# Cosmolink_Sheet.net
KiCad netlist of a schematic drawn in Altium Designer
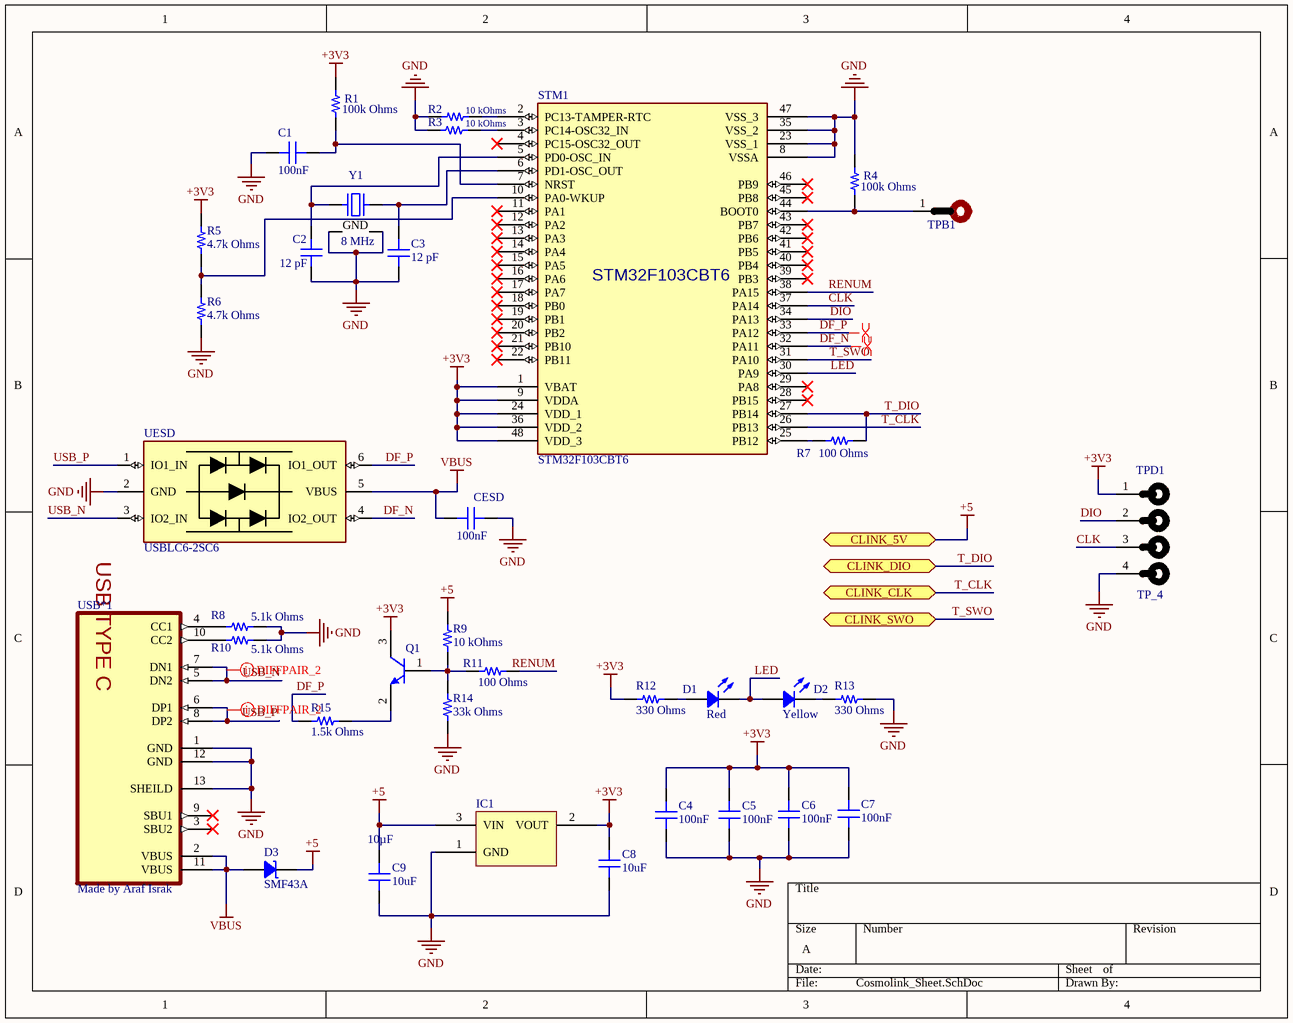
[diagram p0: Cosmolink_Sheet.SchDoc]

(export (version "E")
  (design (tool "Eeschema 10.0.6"))
  (components
    (comp (ref "C1")
      (value "0.1µF")
      (footprint "CAP 0603_1608")
      (description "CAP CER 0.1UF 100V X7R 0603")
      (fields
        (field (name "PART NUMBER") "06031C104KAT2A")
        (field (name "CAPACITANCE") "100nF")
        (field (name "MANUFACTURER") "AVX Corporation")
      )
      (libsource (lib "Celestial Altium Library - altium_library") (part "Capacitor"))
    )
    (comp (ref "C2")
      (value "12 pF")
      (footprint "CAP 0603_1608")
      (description "HIGH-Q MLCC (CF): 0603, 22 PF (1")
      (fields
        (field (name "PART NUMBER") "C06CF220F-9ZN-X0T")
        (field (name "CAPACITANCE") "12 pF")
        (field (name "MANUFACTURER") "Knowles Dielectric Labs")
      )
      (libsource (lib "Celestial Altium Library - altium_library") (part "Capacitor"))
    )
    (comp (ref "C3")
      (value "12 pF")
      (footprint "CAP 0603_1608")
      (description "HIGH-Q MLCC (CF): 0603, 22 PF (1")
      (fields
        (field (name "PART NUMBER") "C06CF220F-9ZN-X0T")
        (field (name "CAPACITANCE") "12 pF")
        (field (name "MANUFACTURER") "Knowles Dielectric Labs")
      )
      (libsource (lib "Celestial Altium Library - altium_library") (part "Capacitor"))
    )
    (comp (ref "C4")
      (value "0.1µF")
      (footprint "CAP 0603_1608")
      (description "CAP CER 0.1UF 100V X7R 0603")
      (fields
        (field (name "PART NUMBER") "06031C104KAT2A")
        (field (name "CAPACITANCE") "100nF")
        (field (name "MANUFACTURER") "AVX Corporation")
      )
      (libsource (lib "Celestial Altium Library - altium_library") (part "Capacitor"))
    )
    (comp (ref "C5")
      (value "0.1µF")
      (footprint "CAP 0603_1608")
      (description "CAP CER 0.1UF 100V X7R 0603")
      (fields
        (field (name "PART NUMBER") "06031C104KAT2A")
        (field (name "CAPACITANCE") "100nF")
        (field (name "MANUFACTURER") "AVX Corporation")
      )
      (libsource (lib "Celestial Altium Library - altium_library") (part "Capacitor"))
    )
    (comp (ref "C6")
      (value "0.1µF")
      (footprint "CAP 0603_1608")
      (description "CAP CER 0.1UF 100V X7R 0603")
      (fields
        (field (name "PART NUMBER") "06031C104KAT2A")
        (field (name "CAPACITANCE") "100nF")
        (field (name "MANUFACTURER") "AVX Corporation")
      )
      (libsource (lib "Celestial Altium Library - altium_library") (part "Capacitor"))
    )
    (comp (ref "C7")
      (value "0.1µF")
      (footprint "CAP 0603_1608")
      (description "CAP CER 0.1UF 100V X7R 0603")
      (fields
        (field (name "PART NUMBER") "06031C104KAT2A")
        (field (name "CAPACITANCE") "100nF")
        (field (name "MANUFACTURER") "AVX Corporation")
      )
      (libsource (lib "Celestial Altium Library - altium_library") (part "Capacitor"))
    )
    (comp (ref "C8")
      (value "10µF")
      (footprint "CAP 0603_1608")
      (description "CAP CER 0.1UF 100V X7R 0603")
      (fields
        (field (name "PART NUMBER") "06031C104KAT2A")
        (field (name "CAPACITANCE") "10uF")
        (field (name "MANUFACTURER") "AVX Corporation")
      )
      (libsource (lib "Celestial Altium Library - altium_library") (part "Capacitor"))
    )
    (comp (ref "C9")
      (value "10µF")
      (footprint "CAP 0603_1608")
      (description "CAP CER 0.1UF 100V X7R 0603")
      (fields
        (field (name "PART NUMBER") "06031C104KAT2A")
        (field (name "CAPACITANCE") "10uF")
        (field (name "MANUFACTURER") "AVX Corporation")
      )
      (libsource (lib "Celestial Altium Library - altium_library") (part "Capacitor"))
    )
    (comp (ref "CESD")
      (value "0.1µF")
      (footprint "CAP 0603_1608")
      (description "CAP CER 0.1UF 100V X7R 0603")
      (fields
        (field (name "PART NUMBER") "06031C104KAT2A")
        (field (name "CAPACITANCE") "100nF")
        (field (name "MANUFACTURER") "AVX Corporation")
      )
      (libsource (lib "Celestial Altium Library - altium_library") (part "Capacitor"))
    )
    (comp (ref "D1")
      (value "Red")
      (footprint "LED 0603_1608 RED")
      (description "LED RED DIFFUSED 1608 SMD")
      (fields
        (field (name "PART NUMBER") "VFHR1111C-3BY2A-TR")
        (field (name "MANUFACTURER") "Stanley Electric Co")
      )
      (libsource (lib "Celestial Altium Library - altium_library") (part "LED"))
    )
    (comp (ref "D2")
      (value "Yellow")
      (footprint "LED 0603_1608 YELLOW")
      (description "LED YELLOW 0603 SMD")
      (fields (field (name "PART NUMBER") "5973405507F") (field (name "MANUFACTURER") "Dialight"))
      (libsource (lib "Celestial Altium Library - altium_library") (part "LED"))
    )
    (comp (ref "D3")
      (value "SMF43A")
      (footprint "SOD123F")
      (description "TVS SOD123FL 43V 200W UNIDIR")
      (fields (field (name "MANUFACTURER") "Littelfuse Inc."))
      (libsource (lib "Celestial Altium Library - altium_library") (part "DIODE TVS UNI"))
    )
    (comp (ref "IC1")
      (value "AP2138N-3.3TRG1")
      (footprint "DIODES SOT-23-3 N")
      (description "IC REG LINEAR 3.3V 250MA SOT23-3")
      (fields (field (name "MANUFACTURER") "Diodes Incorporated"))
      (libsource (lib "Celestial Altium Library - altium_library") (part "Diodes Inc AP2138 3PIN"))
    )
    (comp (ref "Q1")
      (value "DNLS160-7")
      (footprint "DIODES SOT-23-3")
      (description "TRANS NPN 60V 1A SOT23-3")
      (fields (field (name "MANUFACTURER") "Diodes Incorporated"))
      (libsource (lib "Celestial Altium Library - altium_library") (part "DIODES INC NPN SOT-23-3"))
    )
    (comp (ref "R1")
      (value "100k Ohms")
      (footprint "RES 0603_1608")
      (description "RES 10K OHM 0.1% 1/16W 0603")
      (fields
        (field (name "PART NUMBER") "RNCS0603BKE10K0")
        (field (name "MANUFACTURER") "Stackpole Electronics Inc")
      )
      (libsource (lib "Celestial Altium Library - altium_library") (part "Resistor"))
    )
    (comp (ref "R2")
      (value "10 kOhms")
      (footprint "RES 0603_1608")
      (description "RES 10K OHM 0.1% 1/16W 0603")
      (fields
        (field (name "PART NUMBER") "RNCS0603BKE10K0")
        (field (name "MANUFACTURER") "Stackpole Electronics Inc")
      )
      (libsource (lib "Celestial Altium Library - altium_library") (part "Resistor"))
    )
    (comp (ref "R3")
      (value "10 kOhms")
      (footprint "RES 0603_1608")
      (description "RES 10K OHM 0.1% 1/16W 0603")
      (fields
        (field (name "PART NUMBER") "RNCS0603BKE10K0")
        (field (name "MANUFACTURER") "Stackpole Electronics Inc")
      )
      (libsource (lib "Celestial Altium Library - altium_library") (part "Resistor"))
    )
    (comp (ref "R4")
      (value "100k Ohms")
      (footprint "RES 0603_1608")
      (description "RES 10K OHM 0.1% 1/16W 0603")
      (fields
        (field (name "PART NUMBER") "RNCS0603BKE10K0")
        (field (name "MANUFACTURER") "Stackpole Electronics Inc")
      )
      (libsource (lib "Celestial Altium Library - altium_library") (part "Resistor"))
    )
    (comp (ref "R5")
      (value "4.7k Ohms")
      (footprint "RES 0603_1608")
      (description "RES 10K OHM 0.1% 1/16W 0603")
      (fields
        (field (name "PART NUMBER") "RNCS0603BKE10K0")
        (field (name "MANUFACTURER") "Stackpole Electronics Inc")
      )
      (libsource (lib "Celestial Altium Library - altium_library") (part "Resistor"))
    )
    (comp (ref "R6")
      (value "4.7k Ohms")
      (footprint "RES 0603_1608")
      (description "RES 10K OHM 0.1% 1/16W 0603")
      (fields
        (field (name "PART NUMBER") "RNCS0603BKE10K0")
        (field (name "MANUFACTURER") "Stackpole Electronics Inc")
      )
      (libsource (lib "Celestial Altium Library - altium_library") (part "Resistor"))
    )
    (comp (ref "R7")
      (value "100 Ohms")
      (footprint "RES 0603_1608")
      (description "RES 10K OHM 0.1% 1/16W 0603")
      (fields
        (field (name "PART NUMBER") "RNCS0603BKE10K0")
        (field (name "MANUFACTURER") "Stackpole Electronics Inc")
      )
      (libsource (lib "Celestial Altium Library - altium_library") (part "Resistor"))
    )
    (comp (ref "R8")
      (value "5.1k Ohms")
      (footprint "RES 0603_1608")
      (description "RES 10K OHM 0.1% 1/16W 0603")
      (fields
        (field (name "PART NUMBER") "RNCS0603BKE10K0")
        (field (name "MANUFACTURER") "Stackpole Electronics Inc")
      )
      (libsource (lib "Celestial Altium Library - altium_library") (part "Resistor"))
    )
    (comp (ref "R9")
      (value "10 kOhms")
      (footprint "RES 0603_1608")
      (description "RES 10K OHM 0.1% 1/16W 0603")
      (fields
        (field (name "PART NUMBER") "RNCS0603BKE10K0")
        (field (name "MANUFACTURER") "Stackpole Electronics Inc")
      )
      (libsource (lib "Celestial Altium Library - altium_library") (part "Resistor"))
    )
    (comp (ref "R10")
      (value "5.1k Ohms")
      (footprint "RES 0603_1608")
      (description "RES 10K OHM 0.1% 1/16W 0603")
      (fields
        (field (name "PART NUMBER") "RNCS0603BKE10K0")
        (field (name "MANUFACTURER") "Stackpole Electronics Inc")
      )
      (libsource (lib "Celestial Altium Library - altium_library") (part "Resistor"))
    )
    (comp (ref "R11")
      (value "100 Ohms")
      (footprint "RES 0603_1608")
      (description "RES 10K OHM 0.1% 1/16W 0603")
      (fields
        (field (name "PART NUMBER") "RNCS0603BKE10K0")
        (field (name "MANUFACTURER") "Stackpole Electronics Inc")
      )
      (libsource (lib "Celestial Altium Library - altium_library") (part "Resistor"))
    )
    (comp (ref "R12")
      (value "330 Ohms")
      (footprint "RES 0603_1608")
      (description "RES 10K OHM 0.1% 1/16W 0603")
      (fields
        (field (name "PART NUMBER") "RNCS0603BKE10K0")
        (field (name "MANUFACTURER") "Stackpole Electronics Inc")
      )
      (libsource (lib "Celestial Altium Library - altium_library") (part "Resistor"))
    )
    (comp (ref "R13")
      (value "330 Ohms")
      (footprint "RES 0603_1608")
      (description "RES 10K OHM 0.1% 1/16W 0603")
      (fields
        (field (name "PART NUMBER") "RNCS0603BKE10K0")
        (field (name "MANUFACTURER") "Stackpole Electronics Inc")
      )
      (libsource (lib "Celestial Altium Library - altium_library") (part "Resistor"))
    )
    (comp (ref "R14")
      (value "33k Ohms")
      (footprint "RES 0603_1608")
      (description "RES 10K OHM 0.1% 1/16W 0603")
      (fields
        (field (name "PART NUMBER") "RNCS0603BKE10K0")
        (field (name "MANUFACTURER") "Stackpole Electronics Inc")
      )
      (libsource (lib "Celestial Altium Library - altium_library") (part "Resistor"))
    )
    (comp (ref "R15")
      (value "1.5k Ohms")
      (footprint "RES 0603_1608")
      (description "RES 10K OHM 0.1% 1/16W 0603")
      (fields
        (field (name "PART NUMBER") "RNCS0603BKE10K0")
        (field (name "MANUFACTURER") "Stackpole Electronics Inc")
      )
      (libsource (lib "Celestial Altium Library - altium_library") (part "Resistor"))
    )
    (comp (ref "STM1")
      (value "STM32F103CBT6")
      (footprint "STM32F103CBT6_FOOTPRINT")
      (description "128KB 2V~3.6V ARM-M3 20KB 72MHz FLASH 37 LQFP-48(7x7) Microcontrollers (MCU/MPU/SOC) ROHS")
      (fields (field (name "JLCPCB PART #") "C8304"))
      (libsource (lib "ARAF_PERSONAL_INTEGRATED_LIBRARY") (part "STM32F103CBT6"))
    )
    (comp (ref "TPB1") (value "TP_1") (footprint "TP1") (libsource (lib "Schlib1") (part "TP_1")))
    (comp (ref "TPD1") (value "TP_4") (footprint "TP4") (libsource (lib "Schlib1") (part "TP_4")))
    (comp (ref "UESD")
      (value "USBLC6-2SC6")
      (footprint "USBLC6-2SC6_Footprint")
      (fields (field (name "JLCPCB PART #") "C7519"))
      (libsource (lib "ESD_Protection_Components_Series_SCH_Library_ARAF") (part "USBLC6-2"))
    )
    (comp (ref "USB*1")
      (value "Made by Araf Israk")
      (footprint "USB TYPE-C 24P SMD")
      (fields (field (name "LCSC PART") "C2765186"))
      (libsource (lib "USB_Connector_Series_SCH_Library_ARAF") (part "USB TYPE-C 24P SMD"))
    )
    (comp (ref "Y1")
      (value "8 MHz")
      (footprint "EPSON TSX-3225")
      (description "CRYSTAL 16.0000MHZ 16PF SMD")
      (fields (field (name "PART NUMBER") "TSX-3225 16.0000MF10U-B0") (field (name "MANUFACTURER") "EPSON"))
      (libsource (lib "Celestial Altium Library - altium_library") (part "Epson Crystal TSX-3225"))
    )
  )
  (nets
    (net (code "1") (name "+3V3") (class "Default")
      (node (ref "C4") (pin "2") (pinfunction "2_2") (pintype "passive"))
      (node (ref "C5") (pin "2") (pinfunction "2_2") (pintype "passive"))
      (node (ref "C6") (pin "2") (pinfunction "2_2") (pintype "passive"))
      (node (ref "C7") (pin "2") (pinfunction "2_2") (pintype "passive"))
      (node (ref "C8") (pin "2") (pinfunction "2_2") (pintype "passive"))
      (node (ref "IC1") (pin "2") (pinfunction "VOUT_2") (pintype "passive"))
      (node (ref "Q1") (pin "3") (pinfunction "C_3") (pintype "passive"))
      (node (ref "R1") (pin "1") (pinfunction "1_1") (pintype "passive"))
      (node (ref "R12") (pin "1") (pinfunction "1_1") (pintype "passive"))
      (node (ref "R5") (pin "2") (pinfunction "2_2") (pintype "passive"))
      (node (ref "STM1") (pin "1") (pinfunction "VBAT_1") (pintype "power_in"))
      (node (ref "STM1") (pin "24") (pinfunction "VDD_1_24") (pintype "power_in"))
      (node (ref "STM1") (pin "36") (pinfunction "VDD_2_36") (pintype "power_in"))
      (node (ref "STM1") (pin "48") (pinfunction "VDD_3_48") (pintype "power_in"))
      (node (ref "STM1") (pin "9") (pinfunction "VDDA_9") (pintype "power_in"))
      (node (ref "TPD1") (pin "1") (pinfunction "TP1_1") (pintype "passive"))
    )
    (net (code "2") (name "+5") (class "Default")
      (node (ref "C9") (pin "2") (pinfunction "2_2") (pintype "passive"))
      (node (ref "D3") (pin "2") (pinfunction "2_2") (pintype "passive"))
      (node (ref "IC1") (pin "3") (pinfunction "VIN_3") (pintype "passive"))
      (node (ref "R9") (pin "2") (pinfunction "2_2") (pintype "passive"))
    )
    (net (code "3") (name "/CLK") (class "Default")
      (node (ref "STM1") (pin "37") (pinfunction "PA14_37") (pintype "bidirectional"))
      (node (ref "TPD1") (pin "3") (pinfunction "TP3_3") (pintype "passive"))
    )
    (net (code "4") (name "/DF_N") (class "Default")
      (node (ref "STM1") (pin "32") (pinfunction "PA11_32") (pintype "bidirectional"))
      (node (ref "UESD") (pin "4") (pinfunction "IO2_OUT_4") (pintype "bidirectional"))
    )
    (net (code "5") (name "/DF_P") (class "Default")
      (node (ref "R15") (pin "1") (pinfunction "1_1") (pintype "passive"))
      (node (ref "STM1") (pin "33") (pinfunction "PA12_33") (pintype "bidirectional"))
      (node (ref "UESD") (pin "6") (pinfunction "IO1_OUT_6") (pintype "bidirectional"))
    )
    (net (code "6") (name "/DIO") (class "Default")
      (node (ref "STM1") (pin "34") (pinfunction "PA13_34") (pintype "bidirectional"))
      (node (ref "TPD1") (pin "2") (pinfunction "TP2_2") (pintype "passive"))
    )
    (net (code "7") (name "/LED") (class "Default")
      (node (ref "D1") (pin "2") (pinfunction "2_2") (pintype "passive"))
      (node (ref "D2") (pin "1") (pinfunction "1_1") (pintype "passive"))
      (node (ref "STM1") (pin "30") (pinfunction "PA9_30") (pintype "bidirectional"))
    )
    (net (code "8") (name "/RENUM") (class "Default")
      (node (ref "R11") (pin "2") (pinfunction "2_2") (pintype "passive"))
      (node (ref "STM1") (pin "38") (pinfunction "PA15_38") (pintype "bidirectional"))
    )
    (net (code "9") (name "/T_CLK") (class "Default")
      (node (ref "STM1") (pin "26") (pinfunction "PB13_26") (pintype "bidirectional"))
    )
    (net (code "10") (name "/T_DIO") (class "Default")
      (node (ref "R7") (pin "2") (pinfunction "2_2") (pintype "passive"))
      (node (ref "STM1") (pin "27") (pinfunction "PB14_27") (pintype "bidirectional"))
    )
    (net (code "11") (name "/T_SWO") (class "Default")
      (node (ref "STM1") (pin "31") (pinfunction "PA10_31") (pintype "bidirectional"))
    )
    (net (code "12") (name "/USB_N") (class "Default")
      (node (ref "UESD") (pin "3") (pinfunction "IO2_IN_3") (pintype "bidirectional"))
      (node (ref "USB*1") (pin "5") (pinfunction "DN2_5") (pintype "input"))
      (node (ref "USB*1") (pin "7") (pinfunction "DN1_7") (pintype "input"))
    )
    (net (code "13") (name "/USB_P") (class "Default")
      (node (ref "UESD") (pin "1") (pinfunction "IO1_IN_1") (pintype "bidirectional"))
      (node (ref "USB*1") (pin "6") (pinfunction "DP1_6") (pintype "input"))
      (node (ref "USB*1") (pin "8") (pinfunction "DP2_8") (pintype "input"))
    )
    (net (code "14") (name "GND") (class "Default")
      (node (ref "C1") (pin "1") (pinfunction "1_1") (pintype "passive"))
      (node (ref "C2") (pin "1") (pinfunction "1_1") (pintype "passive"))
      (node (ref "C3") (pin "1") (pinfunction "1_1") (pintype "passive"))
      (node (ref "C4") (pin "1") (pinfunction "1_1") (pintype "passive"))
      (node (ref "C5") (pin "1") (pinfunction "1_1") (pintype "passive"))
      (node (ref "C6") (pin "1") (pinfunction "1_1") (pintype "passive"))
      (node (ref "C7") (pin "1") (pinfunction "1_1") (pintype "passive"))
      (node (ref "C8") (pin "1") (pinfunction "1_1") (pintype "passive"))
      (node (ref "C9") (pin "1") (pinfunction "1_1") (pintype "passive"))
      (node (ref "CESD") (pin "1") (pinfunction "1_1") (pintype "passive"))
      (node (ref "IC1") (pin "1") (pinfunction "GND_1") (pintype "passive"))
      (node (ref "R10") (pin "2") (pinfunction "2_2") (pintype "passive"))
      (node (ref "R13") (pin "2") (pinfunction "2_2") (pintype "passive"))
      (node (ref "R14") (pin "1") (pinfunction "1_1") (pintype "passive"))
      (node (ref "R2") (pin "1") (pinfunction "1_1") (pintype "passive"))
      (node (ref "R3") (pin "1") (pinfunction "1_1") (pintype "passive"))
      (node (ref "R4") (pin "1") (pinfunction "1_1") (pintype "passive"))
      (node (ref "R6") (pin "1") (pinfunction "1_1") (pintype "passive"))
      (node (ref "R8") (pin "2") (pinfunction "2_2") (pintype "passive"))
      (node (ref "STM1") (pin "23") (pinfunction "VSS_1_23") (pintype "power_in"))
      (node (ref "STM1") (pin "35") (pinfunction "VSS_2_35") (pintype "power_in"))
      (node (ref "STM1") (pin "47") (pinfunction "VSS_3_47") (pintype "power_in"))
      (node (ref "STM1") (pin "8") (pinfunction "VSSA_8") (pintype "power_in"))
      (node (ref "TPD1") (pin "4") (pinfunction "TP4_4") (pintype "passive"))
      (node (ref "UESD") (pin "2") (pinfunction "GND_2") (pintype "power_in"))
      (node (ref "USB*1") (pin "1") (pinfunction "GND_1") (pintype "power_in"))
      (node (ref "USB*1") (pin "12") (pinfunction "GND_12") (pintype "power_in"))
      (node (ref "USB*1") (pin "13") (pinfunction "SHEILD_13") (pintype "passive"))
      (node (ref "Y1") (pin "2") (pinfunction "GND_2") (pintype "passive"))
      (node (ref "Y1") (pin "4") (pinfunction "GND_4") (pintype "passive"))
    )
    (net (code "15") (name "Net-(D1-Pad1)") (class "Default")
      (node (ref "D1") (pin "1") (pinfunction "1_1") (pintype "passive"))
      (node (ref "R12") (pin "2") (pinfunction "2_2") (pintype "passive"))
    )
    (net (code "16") (name "Net-(D2-Pad2)") (class "Default")
      (node (ref "D2") (pin "2") (pinfunction "2_2") (pintype "passive"))
      (node (ref "R13") (pin "1") (pinfunction "1_1") (pintype "passive"))
    )
    (net (code "17") (name "Net-(Q1-B)") (class "Default")
      (node (ref "Q1") (pin "1") (pinfunction "B_1") (pintype "passive"))
      (node (ref "R11") (pin "1") (pinfunction "1_1") (pintype "passive"))
      (node (ref "R14") (pin "2") (pinfunction "2_2") (pintype "passive"))
      (node (ref "R9") (pin "1") (pinfunction "1_1") (pintype "passive"))
    )
    (net (code "18") (name "Net-(Q1-E)") (class "Default")
      (node (ref "Q1") (pin "2") (pinfunction "E_2") (pintype "passive"))
      (node (ref "R15") (pin "2") (pinfunction "2_2") (pintype "passive"))
    )
    (net (code "19") (name "Net-(STM1-BOOT0)") (class "Default")
      (node (ref "R4") (pin "2") (pinfunction "2_2") (pintype "passive"))
      (node (ref "STM1") (pin "44") (pinfunction "BOOT0_44") (pintype "bidirectional"))
      (node (ref "TPB1") (pin "1") (pinfunction "TP1_1") (pintype "passive"))
    )
    (net (code "20") (name "Net-(STM1-NRST)") (class "Default")
      (node (ref "C1") (pin "2") (pinfunction "2_2") (pintype "passive"))
      (node (ref "R1") (pin "2") (pinfunction "2_2") (pintype "passive"))
      (node (ref "STM1") (pin "7") (pinfunction "NRST_7") (pintype "bidirectional"))
    )
    (net (code "21") (name "Net-(STM1-PA0-WKUP)") (class "Default")
      (node (ref "R5") (pin "1") (pinfunction "1_1") (pintype "passive"))
      (node (ref "R6") (pin "2") (pinfunction "2_2") (pintype "passive"))
      (node (ref "STM1") (pin "10") (pinfunction "PA0-WKUP_10") (pintype "bidirectional"))
    )
    (net (code "22") (name "Net-(STM1-PB12)") (class "Default")
      (node (ref "R7") (pin "1") (pinfunction "1_1") (pintype "passive"))
      (node (ref "STM1") (pin "25") (pinfunction "PB12_25") (pintype "bidirectional"))
    )
    (net (code "23") (name "Net-(STM1-PC13-TAMPER-RTC)") (class "Default")
      (node (ref "R2") (pin "2") (pinfunction "2_2") (pintype "passive"))
      (node (ref "STM1") (pin "2") (pinfunction "PC13-TAMPER-RTC_2") (pintype "bidirectional"))
    )
    (net (code "24") (name "Net-(STM1-PC14-OSC32_IN)") (class "Default")
      (node (ref "R3") (pin "2") (pinfunction "2_2") (pintype "passive"))
      (node (ref "STM1") (pin "3") (pinfunction "PC14-OSC32_IN_3") (pintype "bidirectional"))
    )
    (net (code "25") (name "Net-(STM1-PD0-OSC_IN)") (class "Default")
      (node (ref "C2") (pin "2") (pinfunction "2_2") (pintype "passive"))
      (node (ref "STM1") (pin "5") (pinfunction "PD0-OSC_IN_5") (pintype "bidirectional"))
      (node (ref "Y1") (pin "1") (pinfunction "1_1") (pintype "passive"))
    )
    (net (code "26") (name "Net-(STM1-PD1-OSC_OUT)") (class "Default")
      (node (ref "C3") (pin "2") (pinfunction "2_2") (pintype "passive"))
      (node (ref "STM1") (pin "6") (pinfunction "PD1-OSC_OUT_6") (pintype "bidirectional"))
      (node (ref "Y1") (pin "3") (pinfunction "3_3") (pintype "passive"))
    )
    (net (code "27") (name "Net-(USB*1-CC1)") (class "Default")
      (node (ref "R8") (pin "1") (pinfunction "1_1") (pintype "passive"))
      (node (ref "USB*1") (pin "4") (pinfunction "CC1_4") (pintype "output"))
    )
    (net (code "28") (name "Net-(USB*1-CC2)") (class "Default")
      (node (ref "R10") (pin "1") (pinfunction "1_1") (pintype "passive"))
      (node (ref "USB*1") (pin "10") (pinfunction "CC2_10") (pintype "output"))
    )
    (net (code "29") (name "VBUS") (class "Default")
      (node (ref "CESD") (pin "2") (pinfunction "2_2") (pintype "passive"))
      (node (ref "D3") (pin "1") (pinfunction "1_1") (pintype "passive"))
      (node (ref "UESD") (pin "5") (pinfunction "VBUS_5") (pintype "power_in"))
      (node (ref "USB*1") (pin "11") (pinfunction "VBUS_11") (pintype "power_in"))
      (node (ref "USB*1") (pin "2") (pinfunction "VBUS_2") (pintype "power_in"))
    )
    (net (code "30") (name "unconnected-(STM1-PA1-Pad11)") (class "Default")
      (node (ref "STM1") (pin "11") (pinfunction "PA1_11") (pintype "bidirectional+no_connect"))
    )
    (net (code "31") (name "unconnected-(STM1-PA2-Pad12)") (class "Default")
      (node (ref "STM1") (pin "12") (pinfunction "PA2_12") (pintype "bidirectional+no_connect"))
    )
    (net (code "32") (name "unconnected-(STM1-PA3-Pad13)") (class "Default")
      (node (ref "STM1") (pin "13") (pinfunction "PA3_13") (pintype "bidirectional+no_connect"))
    )
    (net (code "33") (name "unconnected-(STM1-PA4-Pad14)") (class "Default")
      (node (ref "STM1") (pin "14") (pinfunction "PA4_14") (pintype "bidirectional+no_connect"))
    )
    (net (code "34") (name "unconnected-(STM1-PA5-Pad15)") (class "Default")
      (node (ref "STM1") (pin "15") (pinfunction "PA5_15") (pintype "bidirectional+no_connect"))
    )
    (net (code "35") (name "unconnected-(STM1-PA6-Pad16)") (class "Default")
      (node (ref "STM1") (pin "16") (pinfunction "PA6_16") (pintype "bidirectional+no_connect"))
    )
    (net (code "36") (name "unconnected-(STM1-PA7-Pad17)") (class "Default")
      (node (ref "STM1") (pin "17") (pinfunction "PA7_17") (pintype "bidirectional+no_connect"))
    )
    (net (code "37") (name "unconnected-(STM1-PA8-Pad29)") (class "Default")
      (node (ref "STM1") (pin "29") (pinfunction "PA8_29") (pintype "bidirectional+no_connect"))
    )
    (net (code "38") (name "unconnected-(STM1-PB0-Pad18)") (class "Default")
      (node (ref "STM1") (pin "18") (pinfunction "PB0_18") (pintype "bidirectional+no_connect"))
    )
    (net (code "39") (name "unconnected-(STM1-PB1-Pad19)") (class "Default")
      (node (ref "STM1") (pin "19") (pinfunction "PB1_19") (pintype "bidirectional+no_connect"))
    )
    (net (code "40") (name "unconnected-(STM1-PB2-Pad20)") (class "Default")
      (node (ref "STM1") (pin "20") (pinfunction "PB2_20") (pintype "bidirectional+no_connect"))
    )
    (net (code "41") (name "unconnected-(STM1-PB3-Pad39)") (class "Default")
      (node (ref "STM1") (pin "39") (pinfunction "PB3_39") (pintype "bidirectional+no_connect"))
    )
    (net (code "42") (name "unconnected-(STM1-PB4-Pad40)") (class "Default")
      (node (ref "STM1") (pin "40") (pinfunction "PB4_40") (pintype "bidirectional+no_connect"))
    )
    (net (code "43") (name "unconnected-(STM1-PB5-Pad41)") (class "Default")
      (node (ref "STM1") (pin "41") (pinfunction "PB5_41") (pintype "bidirectional+no_connect"))
    )
    (net (code "44") (name "unconnected-(STM1-PB6-Pad42)") (class "Default")
      (node (ref "STM1") (pin "42") (pinfunction "PB6_42") (pintype "bidirectional+no_connect"))
    )
    (net (code "45") (name "unconnected-(STM1-PB7-Pad43)") (class "Default")
      (node (ref "STM1") (pin "43") (pinfunction "PB7_43") (pintype "bidirectional+no_connect"))
    )
    (net (code "46") (name "unconnected-(STM1-PB8-Pad45)") (class "Default")
      (node (ref "STM1") (pin "45") (pinfunction "PB8_45") (pintype "bidirectional+no_connect"))
    )
    (net (code "47") (name "unconnected-(STM1-PB9-Pad46)") (class "Default")
      (node (ref "STM1") (pin "46") (pinfunction "PB9_46") (pintype "bidirectional+no_connect"))
    )
    (net (code "48") (name "unconnected-(STM1-PB10-Pad21)") (class "Default")
      (node (ref "STM1") (pin "21") (pinfunction "PB10_21") (pintype "bidirectional+no_connect"))
    )
    (net (code "49") (name "unconnected-(STM1-PB11-Pad22)") (class "Default")
      (node (ref "STM1") (pin "22") (pinfunction "PB11_22") (pintype "bidirectional+no_connect"))
    )
    (net (code "50") (name "unconnected-(STM1-PB15-Pad28)") (class "Default")
      (node (ref "STM1") (pin "28") (pinfunction "PB15_28") (pintype "bidirectional+no_connect"))
    )
    (net (code "51") (name "unconnected-(STM1-PC15-OSC32_OUT-Pad4)") (class "Default")
      (node (ref "STM1") (pin "4") (pinfunction "PC15-OSC32_OUT_4") (pintype "bidirectional+no_connect"))
    )
    (net (code "52") (name "unconnected-(USB*1-SBU1-Pad9)") (class "Default")
      (node (ref "USB*1") (pin "9") (pinfunction "SBU1_9") (pintype "output+no_connect"))
    )
    (net (code "53") (name "unconnected-(USB*1-SBU2-Pad3)") (class "Default")
      (node (ref "USB*1") (pin "3") (pinfunction "SBU2_3") (pintype "output+no_connect"))
    )
  )
)
